# HelveTiny84.net
KiCad netlist of a schematic drawn in EAGLE
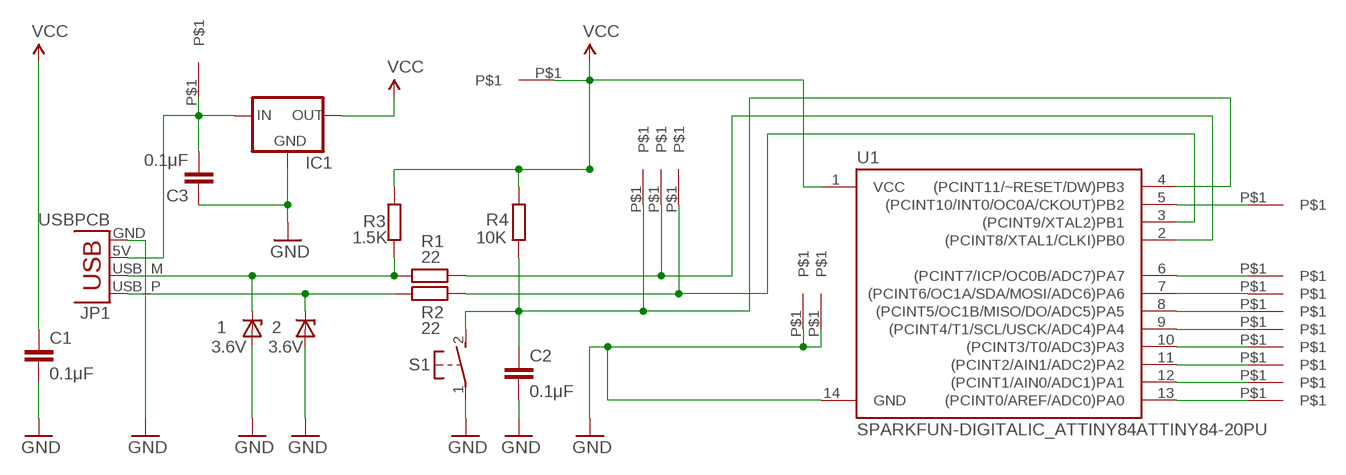
[diagram p0: schematic, sheet 1]

(export (version "E")
  (design (tool "Eeschema 10.0.6"))
  (components
    (comp (ref "1")
      (value "3.6V")
      (footprint "eagle-import:ZDIO-7.5")
      (libsource (lib "eagle-import") (part "ZENER-DIODEZD-7.5"))
    )
    (comp (ref "2")
      (value "3.6V")
      (footprint "eagle-import:ZDIO-7.5")
      (libsource (lib "eagle-import") (part "ZENER-DIODEZD-7.5"))
    )
    (comp (ref "C1")
      (value "0.1μF")
      (footprint "eagle-import:C025-024X044")
      (libsource (lib "eagle-import") (part "C-EU025-024X044"))
    )
    (comp (ref "C2")
      (value "0.1μF")
      (footprint "eagle-import:C025-024X044")
      (libsource (lib "eagle-import") (part "C-EU025-024X044"))
    )
    (comp (ref "C3")
      (value "0.1μF")
      (footprint "eagle-import:C025-024X044")
      (libsource (lib "eagle-import") (part "C-EU025-024X044"))
    )
    (comp (ref "D3")
      (value "FLOWERPIN")
      (footprint "eagle-import:FLOWERPIN")
      (libsource (lib "eagle-import") (part "FLOWERPIN"))
    )
    (comp (ref "D4")
      (value "FLOWERPIN")
      (footprint "eagle-import:FLOWERPIN")
      (libsource (lib "eagle-import") (part "FLOWERPIN"))
    )
    (comp (ref "D5")
      (value "FLOWERPIN")
      (footprint "eagle-import:FLOWERPIN")
      (libsource (lib "eagle-import") (part "FLOWERPIN"))
    )
    (comp (ref "D6")
      (value "FLOWERPIN")
      (footprint "eagle-import:FLOWERPIN")
      (libsource (lib "eagle-import") (part "FLOWERPIN"))
    )
    (comp (ref "D7")
      (value "FLOWERPIN")
      (footprint "eagle-import:FLOWERPIN")
      (libsource (lib "eagle-import") (part "FLOWERPIN"))
    )
    (comp (ref "D8")
      (value "FLOWERPIN")
      (footprint "eagle-import:FLOWERPIN")
      (libsource (lib "eagle-import") (part "FLOWERPIN"))
    )
    (comp (ref "IC1")
      (value "MCP1700TRI")
      (footprint "eagle-import:TO92")
      (libsource (lib "eagle-import") (part "MCP1700TRI"))
    )
    (comp (ref "JP1")
      (value "USBPCB")
      (footprint "eagle-import:USB-A-PCB")
      (libsource (lib "eagle-import") (part "USBPCB"))
    )
    (comp (ref "R1")
      (value "22")
      (footprint "eagle-import:0207_7")
      (libsource (lib "eagle-import") (part "R-EU_0207/7"))
    )
    (comp (ref "R2")
      (value "22")
      (footprint "eagle-import:0207_7")
      (libsource (lib "eagle-import") (part "R-EU_0207/7"))
    )
    (comp (ref "R3")
      (value "1.5K")
      (footprint "eagle-import:0207_7")
      (libsource (lib "eagle-import") (part "R-EU_0207/7"))
    )
    (comp (ref "R4")
      (value "10K")
      (footprint "eagle-import:0207_7")
      (libsource (lib "eagle-import") (part "R-EU_0207/7"))
    )
    (comp (ref "S1")
      (value "S3")
      (footprint "eagle-import:DTS-3")
      (libsource (lib "eagle-import") (part "DTS-3"))
    )
    (comp (ref "TP1")
      (value "FLOWERPIN")
      (footprint "eagle-import:FLOWERPIN")
      (libsource (lib "eagle-import") (part "FLOWERPIN"))
    )
    (comp (ref "TP2")
      (value "FLOWERPIN")
      (footprint "eagle-import:FLOWERPIN")
      (libsource (lib "eagle-import") (part "FLOWERPIN"))
    )
    (comp (ref "TP29")
      (value "FLOWERPIN")
      (footprint "eagle-import:FLOWERPIN")
      (libsource (lib "eagle-import") (part "FLOWERPIN"))
    )
    (comp (ref "TP30")
      (value "FLOWERPIN")
      (footprint "eagle-import:FLOWERPIN")
      (libsource (lib "eagle-import") (part "FLOWERPIN"))
    )
    (comp (ref "TP31")
      (value "FLOWERPIN")
      (footprint "eagle-import:FLOWERPIN")
      (libsource (lib "eagle-import") (part "FLOWERPIN"))
    )
    (comp (ref "TP32")
      (value "FLOWERPIN")
      (footprint "eagle-import:FLOWERPIN")
      (libsource (lib "eagle-import") (part "FLOWERPIN"))
    )
    (comp (ref "TP33")
      (value "FLOWERPIN")
      (footprint "eagle-import:FLOWERPIN")
      (libsource (lib "eagle-import") (part "FLOWERPIN"))
    )
    (comp (ref "TP34")
      (value "FLOWERPIN")
      (footprint "eagle-import:FLOWERPIN")
      (libsource (lib "eagle-import") (part "FLOWERPIN"))
    )
    (comp (ref "TP35")
      (value "FLOWERPIN")
      (footprint "eagle-import:FLOWERPIN")
      (libsource (lib "eagle-import") (part "FLOWERPIN"))
    )
    (comp (ref "TP36")
      (value "FLOWERPIN")
      (footprint "eagle-import:FLOWERPIN")
      (libsource (lib "eagle-import") (part "FLOWERPIN"))
    )
    (comp (ref "U1")
      (value "SPARKFUN-DIGITALIC_ATTINY84ATTINY84-20PU")
      (footprint "eagle-import:SPARKFUN-DIGITALIC_DIL14")
      (libsource (lib "eagle-import") (part "SPARKFUN-DIGITALIC_ATTINY84ATTINY84-20PU"))
    )
  )
  (nets
    (net (code "1") (name "GND") (class "Default")
      (node (ref "1") (pin "A") (pinfunction "A_A") (pintype "passive"))
      (node (ref "2") (pin "A") (pinfunction "A_A") (pintype "passive"))
      (node (ref "C1") (pin "2") (pinfunction "2_2") (pintype "passive"))
      (node (ref "C2") (pin "2") (pinfunction "2_2") (pintype "passive"))
      (node (ref "C3") (pin "1") (pinfunction "1_1") (pintype "passive"))
      (node (ref "IC1") (pin "1") (pinfunction "GND_1") (pintype "input"))
      (node (ref "JP1") (pin "GND") (pinfunction "GND_GND") (pintype "bidirectional"))
      (node (ref "S1") (pin "1") (pinfunction "1_1") (pintype "passive"))
      (node (ref "TP2") (pin "P$1") (pinfunction "P$1_P$1") (pintype "bidirectional"))
      (node (ref "TP32") (pin "P$1") (pinfunction "P$1_P$1") (pintype "bidirectional"))
      (node (ref "U1") (pin "14") (pinfunction "GND_14") (pintype "bidirectional"))
    )
    (net (code "2") (name "Net-(IC1-IN)") (class "Default")
      (node (ref "C3") (pin "2") (pinfunction "2_2") (pintype "passive"))
      (node (ref "IC1") (pin "2") (pinfunction "IN_2") (pintype "input"))
      (node (ref "JP1") (pin "5V") (pinfunction "VBUS_5V") (pintype "bidirectional"))
      (node (ref "TP1") (pin "P$1") (pinfunction "P$1_P$1") (pintype "bidirectional"))
    )
    (net (code "3") (name "Net-(JP1-D+)") (class "Default")
      (node (ref "2") (pin "C") (pinfunction "C_C") (pintype "passive"))
      (node (ref "JP1") (pin "USB_P") (pinfunction "D+_USB_P") (pintype "bidirectional"))
      (node (ref "R2") (pin "1") (pinfunction "1_1") (pintype "passive"))
    )
    (net (code "4") (name "Net-(JP1-D-)") (class "Default")
      (node (ref "1") (pin "C") (pinfunction "C_C") (pintype "passive"))
      (node (ref "JP1") (pin "USB_M") (pinfunction "D-_USB_M") (pintype "bidirectional"))
      (node (ref "R1") (pin "1") (pinfunction "1_1") (pintype "passive"))
      (node (ref "R3") (pin "1") (pinfunction "1_1") (pintype "passive"))
    )
    (net (code "5") (name "Net-(U1-(PCINT0{slash}AREF{slash}ADC0)PA0)") (class "Default")
      (node (ref "TP33") (pin "P$1") (pinfunction "P$1_P$1") (pintype "bidirectional"))
      (node (ref "U1") (pin "13") (pinfunction "(PCINT0/AREF/ADC0)PA0_13") (pintype "bidirectional"))
    )
    (net (code "6") (name "Net-(U1-(PCINT1{slash}AIN0{slash}ADC1)PA1)") (class "Default")
      (node (ref "TP34") (pin "P$1") (pinfunction "P$1_P$1") (pintype "bidirectional"))
      (node (ref "U1") (pin "12") (pinfunction "(PCINT1/AIN0/ADC1)PA1_12") (pintype "bidirectional"))
    )
    (net (code "7") (name "Net-(U1-(PCINT2{slash}AIN1{slash}ADC2)PA2)") (class "Default")
      (node (ref "TP35") (pin "P$1") (pinfunction "P$1_P$1") (pintype "bidirectional"))
      (node (ref "U1") (pin "11") (pinfunction "(PCINT2/AIN1/ADC2)PA2_11") (pintype "bidirectional"))
    )
    (net (code "8") (name "Net-(U1-(PCINT3{slash}T0{slash}ADC3)PA3)") (class "Default")
      (node (ref "D3") (pin "P$1") (pinfunction "P$1_P$1") (pintype "bidirectional"))
      (node (ref "U1") (pin "10") (pinfunction "(PCINT3/T0/ADC3)PA3_10") (pintype "bidirectional"))
    )
    (net (code "9") (name "Net-(U1-(PCINT4{slash}T1{slash}SCL{slash}USCK{slash}ADC4)PA4)") (class "Default")
      (node (ref "D4") (pin "P$1") (pinfunction "P$1_P$1") (pintype "bidirectional"))
      (node (ref "U1") (pin "9") (pinfunction "(PCINT4/T1/SCL/USCK/ADC4)PA4_9") (pintype "bidirectional"))
    )
    (net (code "10") (name "Net-(U1-(PCINT5{slash}OC1B{slash}MISO{slash}DO{slash}ADC5)PA5)") (class "Default")
      (node (ref "D5") (pin "P$1") (pinfunction "P$1_P$1") (pintype "bidirectional"))
      (node (ref "U1") (pin "8") (pinfunction "(PCINT5/OC1B/MISO/DO/ADC5)PA5_8") (pintype "bidirectional"))
    )
    (net (code "11") (name "Net-(U1-(PCINT6{slash}OC1A{slash}SDA{slash}MOSI{slash}ADC6)PA6)") (class "Default")
      (node (ref "D6") (pin "P$1") (pinfunction "P$1_P$1") (pintype "bidirectional"))
      (node (ref "U1") (pin "7") (pinfunction "(PCINT6/OC1A/SDA/MOSI/ADC6)PA6_7") (pintype "bidirectional"))
    )
    (net (code "12") (name "Net-(U1-(PCINT7{slash}ICP{slash}OC0B{slash}ADC7)PA7)") (class "Default")
      (node (ref "D7") (pin "P$1") (pinfunction "P$1_P$1") (pintype "bidirectional"))
      (node (ref "U1") (pin "6") (pinfunction "(PCINT7/ICP/OC0B/ADC7)PA7_6") (pintype "bidirectional"))
    )
    (net (code "13") (name "Net-(U1-(PCINT8{slash}XTAL1{slash}CLKI)PB0)") (class "Default")
      (node (ref "R1") (pin "2") (pinfunction "2_2") (pintype "passive"))
      (node (ref "TP30") (pin "P$1") (pinfunction "P$1_P$1") (pintype "bidirectional"))
      (node (ref "U1") (pin "2") (pinfunction "(PCINT8/XTAL1/CLKI)PB0_2") (pintype "bidirectional"))
    )
    (net (code "14") (name "Net-(U1-(PCINT9{slash}XTAL2)PB1)") (class "Default")
      (node (ref "R2") (pin "2") (pinfunction "2_2") (pintype "passive"))
      (node (ref "TP31") (pin "P$1") (pinfunction "P$1_P$1") (pintype "bidirectional"))
      (node (ref "U1") (pin "3") (pinfunction "(PCINT9/XTAL2)PB1_3") (pintype "bidirectional"))
    )
    (net (code "15") (name "Net-(U1-(PCINT10{slash}INT0{slash}OC0A{slash}CKOUT)PB2)") (class "Default")
      (node (ref "D8") (pin "P$1") (pinfunction "P$1_P$1") (pintype "bidirectional"))
      (node (ref "U1") (pin "5") (pinfunction "(PCINT10/INT0/OC0A/CKOUT)PB2_5") (pintype "bidirectional"))
    )
    (net (code "16") (name "Net-(U1-(PCINT11{slash}~{RESET{slash}DW})PB3)") (class "Default")
      (node (ref "C2") (pin "1") (pinfunction "1_1") (pintype "passive"))
      (node (ref "R4") (pin "1") (pinfunction "1_1") (pintype "passive"))
      (node (ref "S1") (pin "2") (pinfunction "2_2") (pintype "passive"))
      (node (ref "TP29") (pin "P$1") (pinfunction "P$1_P$1") (pintype "bidirectional"))
      (node (ref "U1") (pin "4") (pinfunction "(PCINT11/~{RESET/DW})PB3_4") (pintype "bidirectional"))
    )
    (net (code "17") (name "VCC") (class "Default")
      (node (ref "C1") (pin "1") (pinfunction "1_1") (pintype "passive"))
      (node (ref "IC1") (pin "3") (pinfunction "OUT_3") (pintype "passive"))
      (node (ref "R3") (pin "2") (pinfunction "2_2") (pintype "passive"))
      (node (ref "R4") (pin "2") (pinfunction "2_2") (pintype "passive"))
      (node (ref "TP36") (pin "P$1") (pinfunction "P$1_P$1") (pintype "bidirectional"))
      (node (ref "U1") (pin "1") (pinfunction "VCC_1") (pintype "bidirectional"))
    )
  )
)
